# H-bridge.net
KiCad netlist of a schematic drawn in EAGLE
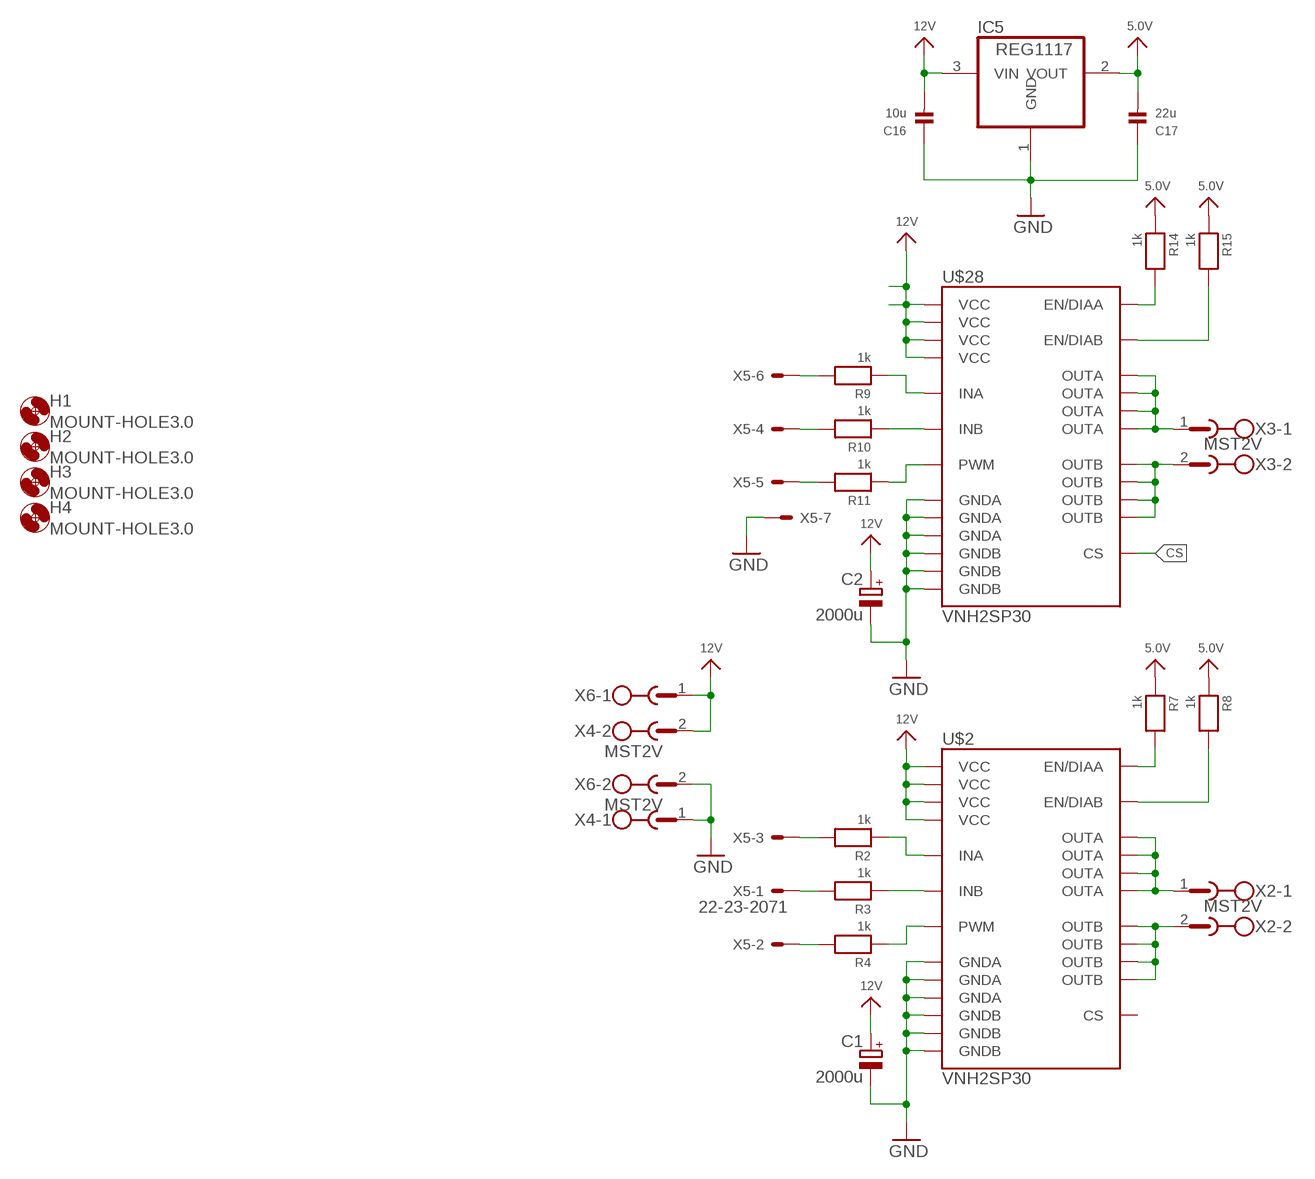
[diagram p0: schematic, sheet 1]

(export (version "E")
  (design (tool "Eeschema 10.0.6"))
  (components
    (comp (ref "C1")
      (value "2000u")
      (footprint "eagle-import:EB22,5D")
      (libsource (lib "eagle-import") (part "CPOL-EUE10-22.5"))
    )
    (comp (ref "C2")
      (value "2000u")
      (footprint "eagle-import:EB22,5D")
      (libsource (lib "eagle-import") (part "CPOL-EUE10-22.5"))
    )
    (comp (ref "C16")
      (value "10u")
      (footprint "eagle-import:_0805")
      (libsource (lib "eagle-import") (part "CAP_CERAMIC_0805"))
    )
    (comp (ref "C17")
      (value "22u")
      (footprint "eagle-import:_0805")
      (libsource (lib "eagle-import") (part "CAP_CERAMIC_0805"))
    )
    (comp (ref "H1")
      (value "MOUNT-HOLE3.0")
      (footprint "eagle-import:3,0")
      (libsource (lib "eagle-import") (part "MOUNT-HOLE3.0"))
    )
    (comp (ref "H2")
      (value "MOUNT-HOLE3.0")
      (footprint "eagle-import:3,0")
      (libsource (lib "eagle-import") (part "MOUNT-HOLE3.0"))
    )
    (comp (ref "H3")
      (value "MOUNT-HOLE3.0")
      (footprint "eagle-import:3,0")
      (libsource (lib "eagle-import") (part "MOUNT-HOLE3.0"))
    )
    (comp (ref "H4")
      (value "MOUNT-HOLE3.0")
      (footprint "eagle-import:3,0")
      (libsource (lib "eagle-import") (part "MOUNT-HOLE3.0"))
    )
    (comp (ref "IC5")
      (value "REG1117")
      (footprint "eagle-import:SOT223")
      (libsource (lib "eagle-import") (part "REG1117"))
    )
    (comp (ref "R2")
      (value "1k")
      (footprint "eagle-import:_0603")
      (libsource (lib "eagle-import") (part "RESISTOR_0603"))
    )
    (comp (ref "R3")
      (value "1k")
      (footprint "eagle-import:_0603")
      (libsource (lib "eagle-import") (part "RESISTOR_0603"))
    )
    (comp (ref "R4")
      (value "1k")
      (footprint "eagle-import:_0603")
      (libsource (lib "eagle-import") (part "RESISTOR_0603"))
    )
    (comp (ref "R7")
      (value "1k")
      (footprint "eagle-import:_0603")
      (libsource (lib "eagle-import") (part "RESISTOR_0603"))
    )
    (comp (ref "R8")
      (value "1k")
      (footprint "eagle-import:_0603")
      (libsource (lib "eagle-import") (part "RESISTOR_0603"))
    )
    (comp (ref "R9")
      (value "1k")
      (footprint "eagle-import:_0603")
      (libsource (lib "eagle-import") (part "RESISTOR_0603"))
    )
    (comp (ref "R10")
      (value "1k")
      (footprint "eagle-import:_0603")
      (libsource (lib "eagle-import") (part "RESISTOR_0603"))
    )
    (comp (ref "R11")
      (value "1k")
      (footprint "eagle-import:_0603")
      (libsource (lib "eagle-import") (part "RESISTOR_0603"))
    )
    (comp (ref "R14")
      (value "1k")
      (footprint "eagle-import:_0603")
      (libsource (lib "eagle-import") (part "RESISTOR_0603"))
    )
    (comp (ref "R15")
      (value "1k")
      (footprint "eagle-import:_0603")
      (libsource (lib "eagle-import") (part "RESISTOR_0603"))
    )
    (comp (ref "U$2")
      (value "VNH2SP30")
      (footprint "eagle-import:VNH2SP30")
      (libsource (lib "eagle-import") (part "VNH2SP30"))
    )
    (comp (ref "U$28")
      (value "VNH2SP30")
      (footprint "eagle-import:VNH2SP30")
      (libsource (lib "eagle-import") (part "VNH2SP30"))
    )
    (comp (ref "X2")
      (value "MST2V")
      (footprint "eagle-import:MSTBV2")
      (libsource (lib "eagle-import") (part "MST2V"))
    )
    (comp (ref "X3")
      (value "MST2V")
      (footprint "eagle-import:MSTBV2")
      (libsource (lib "eagle-import") (part "MST2V"))
    )
    (comp (ref "X4")
      (value "MST2V")
      (footprint "eagle-import:MSTBV2")
      (libsource (lib "eagle-import") (part "MST2V"))
    )
    (comp (ref "X5")
      (value "22-23-2071")
      (footprint "eagle-import:22-23-2071")
      (fields (field (name "MF") "MOLEX"))
      (libsource (lib "eagle-import") (part "22-23-2071"))
    )
    (comp (ref "X6")
      (value "MST2V")
      (footprint "eagle-import:MSTBV2")
      (libsource (lib "eagle-import") (part "MST2V"))
    )
  )
  (nets
    (net (code "1") (name "5.0V") (class "Default")
      (node (ref "C17") (pin "2") (pinfunction "P$2_2") (pintype "passive"))
      (node (ref "IC5") (pin "2") (pinfunction "VOUT_2") (pintype "output"))
      (node (ref "R14") (pin "1") (pinfunction "1_1") (pintype "passive"))
      (node (ref "R15") (pin "1") (pinfunction "1_1") (pintype "passive"))
      (node (ref "R7") (pin "1") (pinfunction "1_1") (pintype "passive"))
      (node (ref "R8") (pin "1") (pinfunction "1_1") (pintype "passive"))
    )
    (net (code "2") (name "12V") (class "Default")
      (node (ref "C1") (pin "+") (pinfunction "+_+") (pintype "passive"))
      (node (ref "C16") (pin "2") (pinfunction "P$2_2") (pintype "passive"))
      (node (ref "C2") (pin "+") (pinfunction "+_+") (pintype "passive"))
      (node (ref "IC5") (pin "3") (pinfunction "VIN_3") (pintype "input"))
      (node (ref "U$2") (pin "13") (pinfunction "VCC_13") (pintype "bidirectional"))
      (node (ref "U$2") (pin "23") (pinfunction "VCC_23") (pintype "bidirectional"))
      (node (ref "U$2") (pin "3") (pinfunction "VCC_3") (pintype "bidirectional"))
      (node (ref "U$2") (pin "SLUG1") (pinfunction "VCC_SLUG1") (pintype "bidirectional"))
      (node (ref "U$28") (pin "13") (pinfunction "VCC_13") (pintype "bidirectional"))
      (node (ref "U$28") (pin "23") (pinfunction "VCC_23") (pintype "bidirectional"))
      (node (ref "U$28") (pin "3") (pinfunction "VCC_3") (pintype "bidirectional"))
      (node (ref "U$28") (pin "SLUG1") (pinfunction "VCC_SLUG1") (pintype "bidirectional"))
      (node (ref "X4") (pin "2") (pinfunction "1_2") (pintype "passive"))
      (node (ref "X6") (pin "1") (pinfunction "1_1") (pintype "passive"))
    )
    (net (code "3") (name "CS") (class "Default")
      (node (ref "U$28") (pin "9") (pinfunction "CS_9") (pintype "bidirectional"))
    )
    (net (code "4") (name "GND") (class "Default")
      (node (ref "C1") (pin "-") (pinfunction "-_-") (pintype "passive"))
      (node (ref "C16") (pin "1") (pinfunction "P$1_1") (pintype "passive"))
      (node (ref "C17") (pin "1") (pinfunction "P$1_1") (pintype "passive"))
      (node (ref "C2") (pin "-") (pinfunction "-_-") (pintype "passive"))
      (node (ref "IC5") (pin "1") (pinfunction "GND_1") (pintype "power_in"))
      (node (ref "U$2") (pin "18") (pinfunction "GNDB_18") (pintype "bidirectional"))
      (node (ref "U$2") (pin "19") (pinfunction "GNDB_19") (pintype "bidirectional"))
      (node (ref "U$2") (pin "20") (pinfunction "GNDB_20") (pintype "bidirectional"))
      (node (ref "U$2") (pin "26") (pinfunction "GNDA_26") (pintype "bidirectional"))
      (node (ref "U$2") (pin "27") (pinfunction "GNDA_27") (pintype "bidirectional"))
      (node (ref "U$2") (pin "28") (pinfunction "GNDA_28") (pintype "bidirectional"))
      (node (ref "U$28") (pin "18") (pinfunction "GNDB_18") (pintype "bidirectional"))
      (node (ref "U$28") (pin "19") (pinfunction "GNDB_19") (pintype "bidirectional"))
      (node (ref "U$28") (pin "20") (pinfunction "GNDB_20") (pintype "bidirectional"))
      (node (ref "U$28") (pin "26") (pinfunction "GNDA_26") (pintype "bidirectional"))
      (node (ref "U$28") (pin "27") (pinfunction "GNDA_27") (pintype "bidirectional"))
      (node (ref "U$28") (pin "28") (pinfunction "GNDA_28") (pintype "bidirectional"))
      (node (ref "X4") (pin "1") (pinfunction "1_1") (pintype "passive"))
      (node (ref "X5") (pin "7") (pinfunction "S_7") (pintype "passive"))
      (node (ref "X6") (pin "2") (pinfunction "1_2") (pintype "passive"))
    )
    (net (code "5") (name "Net-(U$2-EN{slash}DIAA)") (class "Default")
      (node (ref "R7") (pin "2") (pinfunction "2_2") (pintype "passive"))
      (node (ref "U$2") (pin "6") (pinfunction "EN/DIAA_6") (pintype "bidirectional"))
    )
    (net (code "6") (name "Net-(U$2-EN{slash}DIAB)") (class "Default")
      (node (ref "R8") (pin "2") (pinfunction "2_2") (pintype "passive"))
      (node (ref "U$2") (pin "10") (pinfunction "EN/DIAB_10") (pintype "bidirectional"))
    )
    (net (code "7") (name "Net-(U$2-INA)") (class "Default")
      (node (ref "R2") (pin "1") (pinfunction "1_1") (pintype "passive"))
      (node (ref "U$2") (pin "5") (pinfunction "INA_5") (pintype "bidirectional"))
    )
    (net (code "8") (name "Net-(U$2-INB)") (class "Default")
      (node (ref "R3") (pin "1") (pinfunction "1_1") (pintype "passive"))
      (node (ref "U$2") (pin "11") (pinfunction "INB_11") (pintype "bidirectional"))
    )
    (net (code "9") (name "Net-(U$2-OUTA-Pad1)") (class "Default")
      (node (ref "U$2") (pin "1") (pinfunction "OUTA_1") (pintype "bidirectional"))
      (node (ref "U$2") (pin "25") (pinfunction "OUTA_25") (pintype "bidirectional"))
      (node (ref "U$2") (pin "30") (pinfunction "OUTA_30") (pintype "bidirectional"))
      (node (ref "U$2") (pin "SLUG3") (pinfunction "OUTA_SLUG3") (pintype "bidirectional"))
      (node (ref "X2") (pin "1") (pinfunction "1_1") (pintype "passive"))
    )
    (net (code "10") (name "Net-(U$2-PWM)") (class "Default")
      (node (ref "R4") (pin "1") (pinfunction "1_1") (pintype "passive"))
      (node (ref "U$2") (pin "8") (pinfunction "PWM_8") (pintype "bidirectional"))
    )
    (net (code "11") (name "Net-(U$28-EN{slash}DIAA)") (class "Default")
      (node (ref "R14") (pin "2") (pinfunction "2_2") (pintype "passive"))
      (node (ref "U$28") (pin "6") (pinfunction "EN/DIAA_6") (pintype "bidirectional"))
    )
    (net (code "12") (name "Net-(U$28-EN{slash}DIAB)") (class "Default")
      (node (ref "R15") (pin "2") (pinfunction "2_2") (pintype "passive"))
      (node (ref "U$28") (pin "10") (pinfunction "EN/DIAB_10") (pintype "bidirectional"))
    )
    (net (code "13") (name "Net-(U$28-INA)") (class "Default")
      (node (ref "R9") (pin "1") (pinfunction "1_1") (pintype "passive"))
      (node (ref "U$28") (pin "5") (pinfunction "INA_5") (pintype "bidirectional"))
    )
    (net (code "14") (name "Net-(U$28-INB)") (class "Default")
      (node (ref "R10") (pin "1") (pinfunction "1_1") (pintype "passive"))
      (node (ref "U$28") (pin "11") (pinfunction "INB_11") (pintype "bidirectional"))
    )
    (net (code "15") (name "Net-(U$28-OUTA-Pad1)") (class "Default")
      (node (ref "U$28") (pin "1") (pinfunction "OUTA_1") (pintype "bidirectional"))
      (node (ref "U$28") (pin "25") (pinfunction "OUTA_25") (pintype "bidirectional"))
      (node (ref "U$28") (pin "30") (pinfunction "OUTA_30") (pintype "bidirectional"))
      (node (ref "U$28") (pin "SLUG3") (pinfunction "OUTA_SLUG3") (pintype "bidirectional"))
      (node (ref "X3") (pin "1") (pinfunction "1_1") (pintype "passive"))
    )
    (net (code "16") (name "Net-(U$28-PWM)") (class "Default")
      (node (ref "R11") (pin "1") (pinfunction "1_1") (pintype "passive"))
      (node (ref "U$28") (pin "8") (pinfunction "PWM_8") (pintype "bidirectional"))
    )
    (net (code "17") (name "Net-(X2B-1)") (class "Default")
      (node (ref "U$2") (pin "15") (pinfunction "OUTB_15") (pintype "bidirectional"))
      (node (ref "U$2") (pin "16") (pinfunction "OUTB_16") (pintype "bidirectional"))
      (node (ref "U$2") (pin "21") (pinfunction "OUTB_21") (pintype "bidirectional"))
      (node (ref "U$2") (pin "SLUG2") (pinfunction "OUTB_SLUG2") (pintype "bidirectional"))
      (node (ref "X2") (pin "2") (pinfunction "1_2") (pintype "passive"))
    )
    (net (code "18") (name "Net-(X3B-1)") (class "Default")
      (node (ref "U$28") (pin "15") (pinfunction "OUTB_15") (pintype "bidirectional"))
      (node (ref "U$28") (pin "16") (pinfunction "OUTB_16") (pintype "bidirectional"))
      (node (ref "U$28") (pin "21") (pinfunction "OUTB_21") (pintype "bidirectional"))
      (node (ref "U$28") (pin "SLUG2") (pinfunction "OUTB_SLUG2") (pintype "bidirectional"))
      (node (ref "X3") (pin "2") (pinfunction "1_2") (pintype "passive"))
    )
    (net (code "19") (name "Net-(X5A-S)") (class "Default")
      (node (ref "R3") (pin "2") (pinfunction "2_2") (pintype "passive"))
      (node (ref "X5") (pin "1") (pinfunction "S_1") (pintype "passive"))
    )
    (net (code "20") (name "Net-(X5B-S)") (class "Default")
      (node (ref "R4") (pin "2") (pinfunction "2_2") (pintype "passive"))
      (node (ref "X5") (pin "2") (pinfunction "S_2") (pintype "passive"))
    )
    (net (code "21") (name "Net-(X5C-S)") (class "Default")
      (node (ref "R2") (pin "2") (pinfunction "2_2") (pintype "passive"))
      (node (ref "X5") (pin "3") (pinfunction "S_3") (pintype "passive"))
    )
    (net (code "22") (name "Net-(X5D-S)") (class "Default")
      (node (ref "R10") (pin "2") (pinfunction "2_2") (pintype "passive"))
      (node (ref "X5") (pin "4") (pinfunction "S_4") (pintype "passive"))
    )
    (net (code "23") (name "Net-(X5E-S)") (class "Default")
      (node (ref "R11") (pin "2") (pinfunction "2_2") (pintype "passive"))
      (node (ref "X5") (pin "5") (pinfunction "S_5") (pintype "passive"))
    )
    (net (code "24") (name "Net-(X5F-S)") (class "Default")
      (node (ref "R9") (pin "2") (pinfunction "2_2") (pintype "passive"))
      (node (ref "X5") (pin "6") (pinfunction "S_6") (pintype "passive"))
    )
    (net (code "25") (name "unconnected-(U$2-CS-Pad9)") (class "Default")
      (node (ref "U$2") (pin "9") (pinfunction "CS_9") (pintype "bidirectional"))
    )
  )
)
